# FPGA.net
KiCad netlist of a schematic drawn in Altium Designer
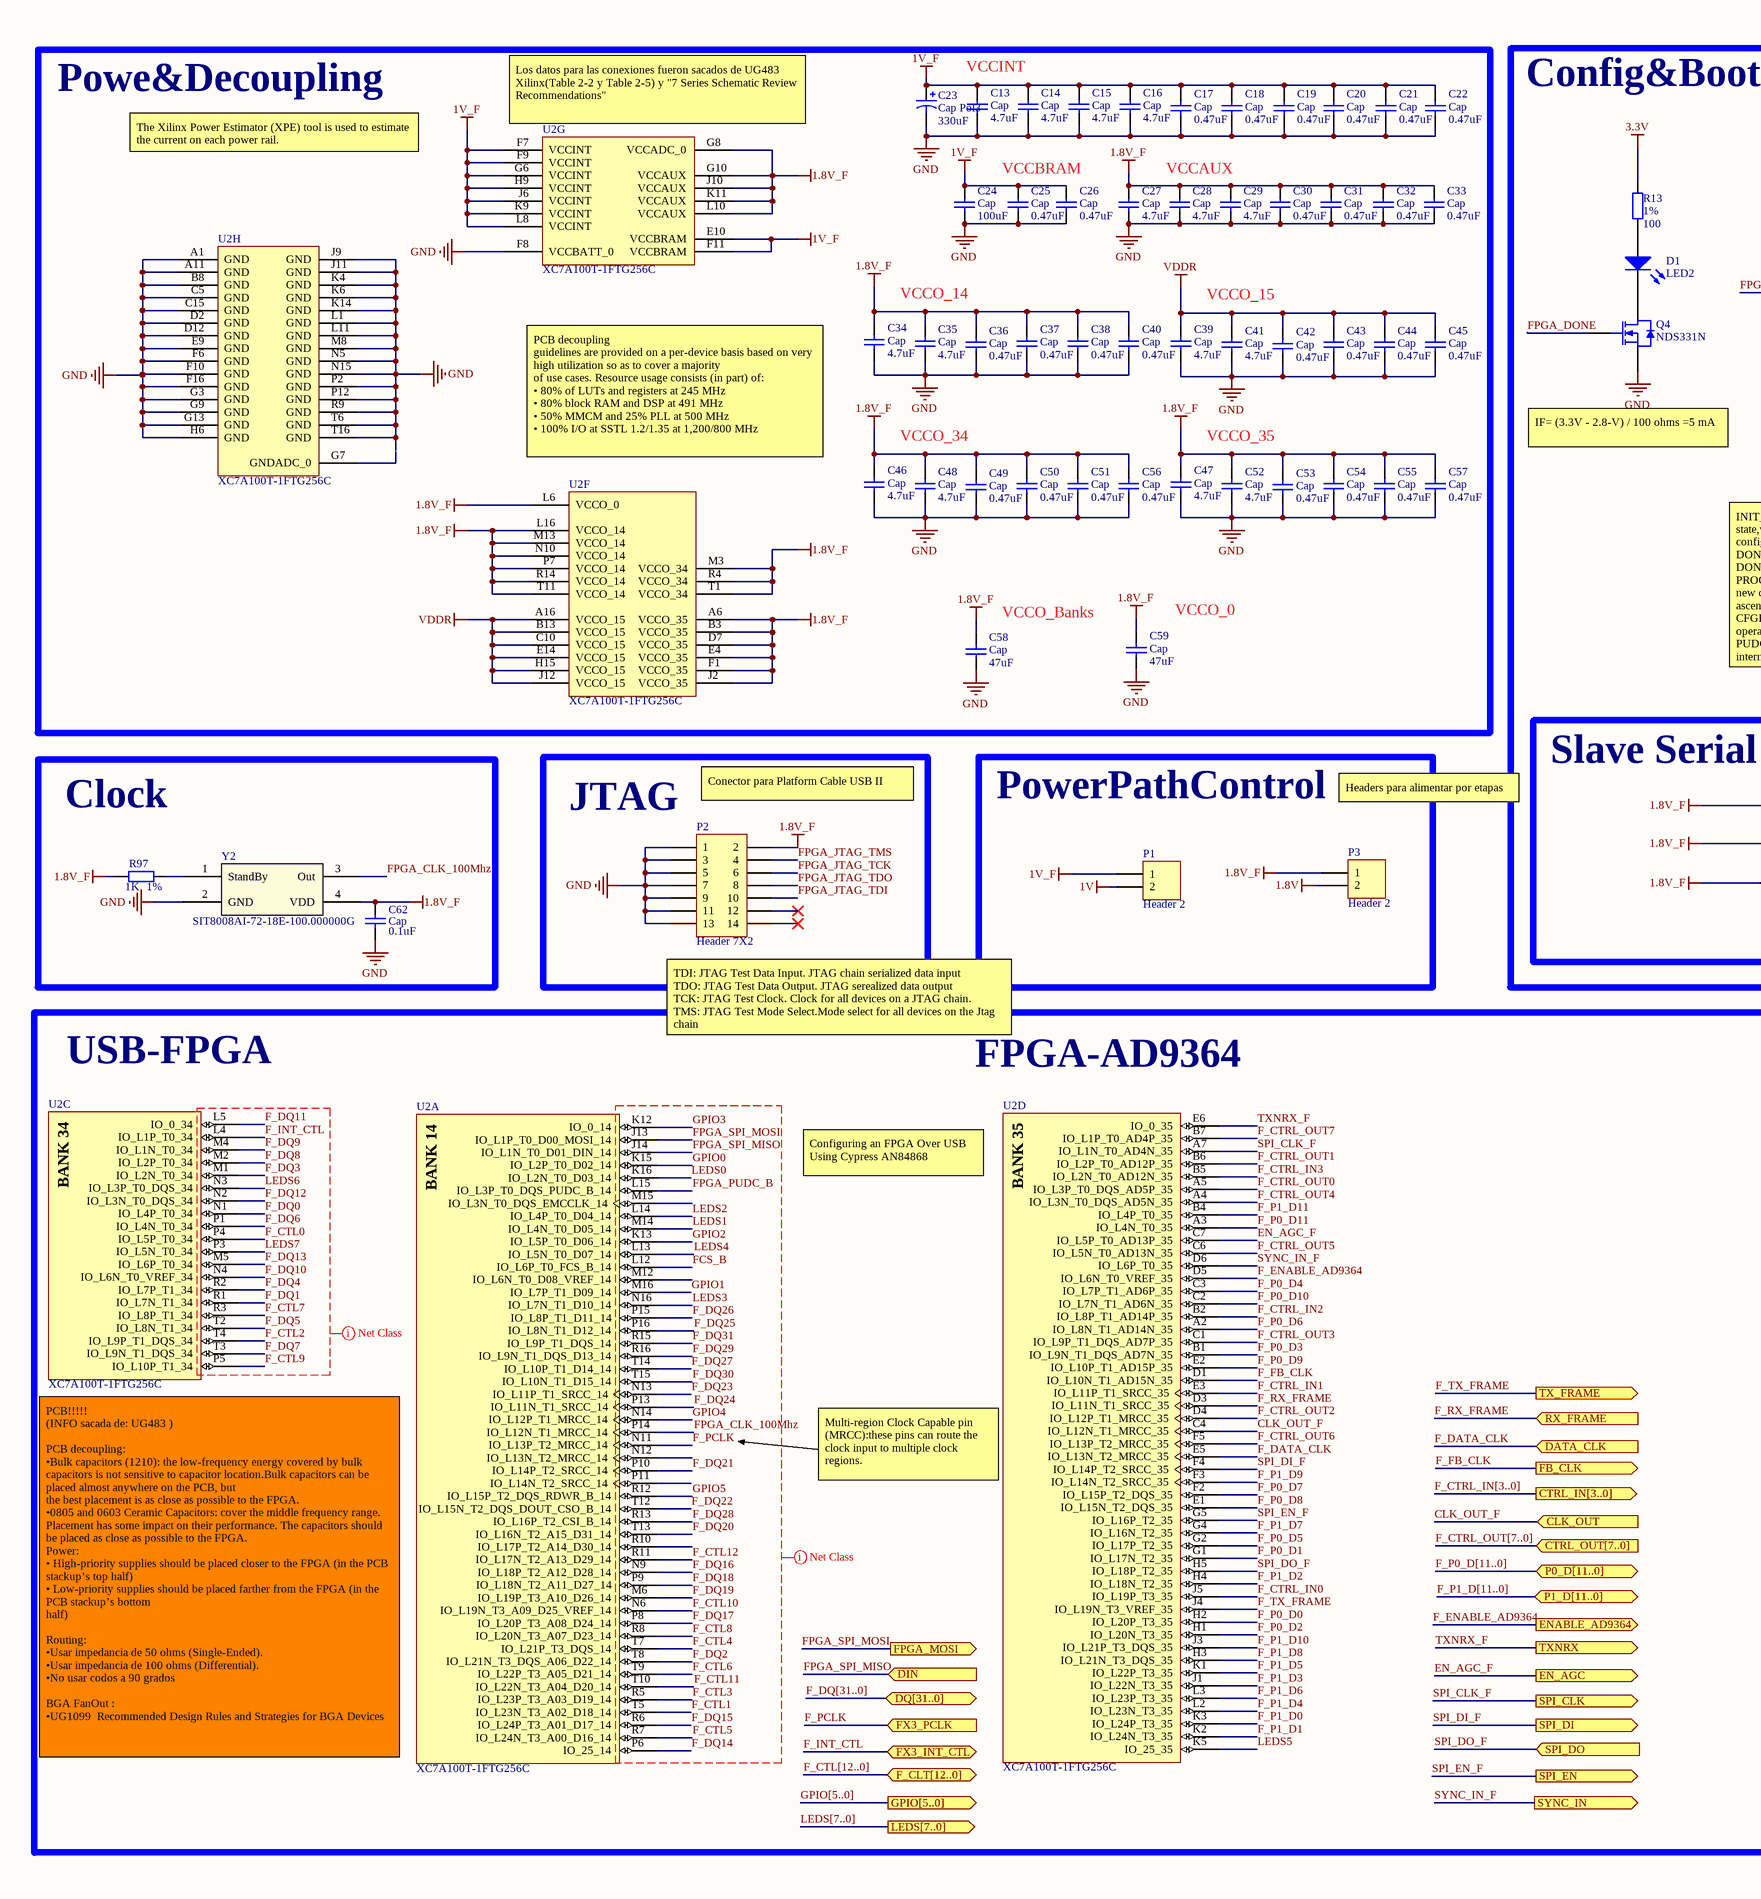
[diagram p0: FPGA.SchDoc, left]
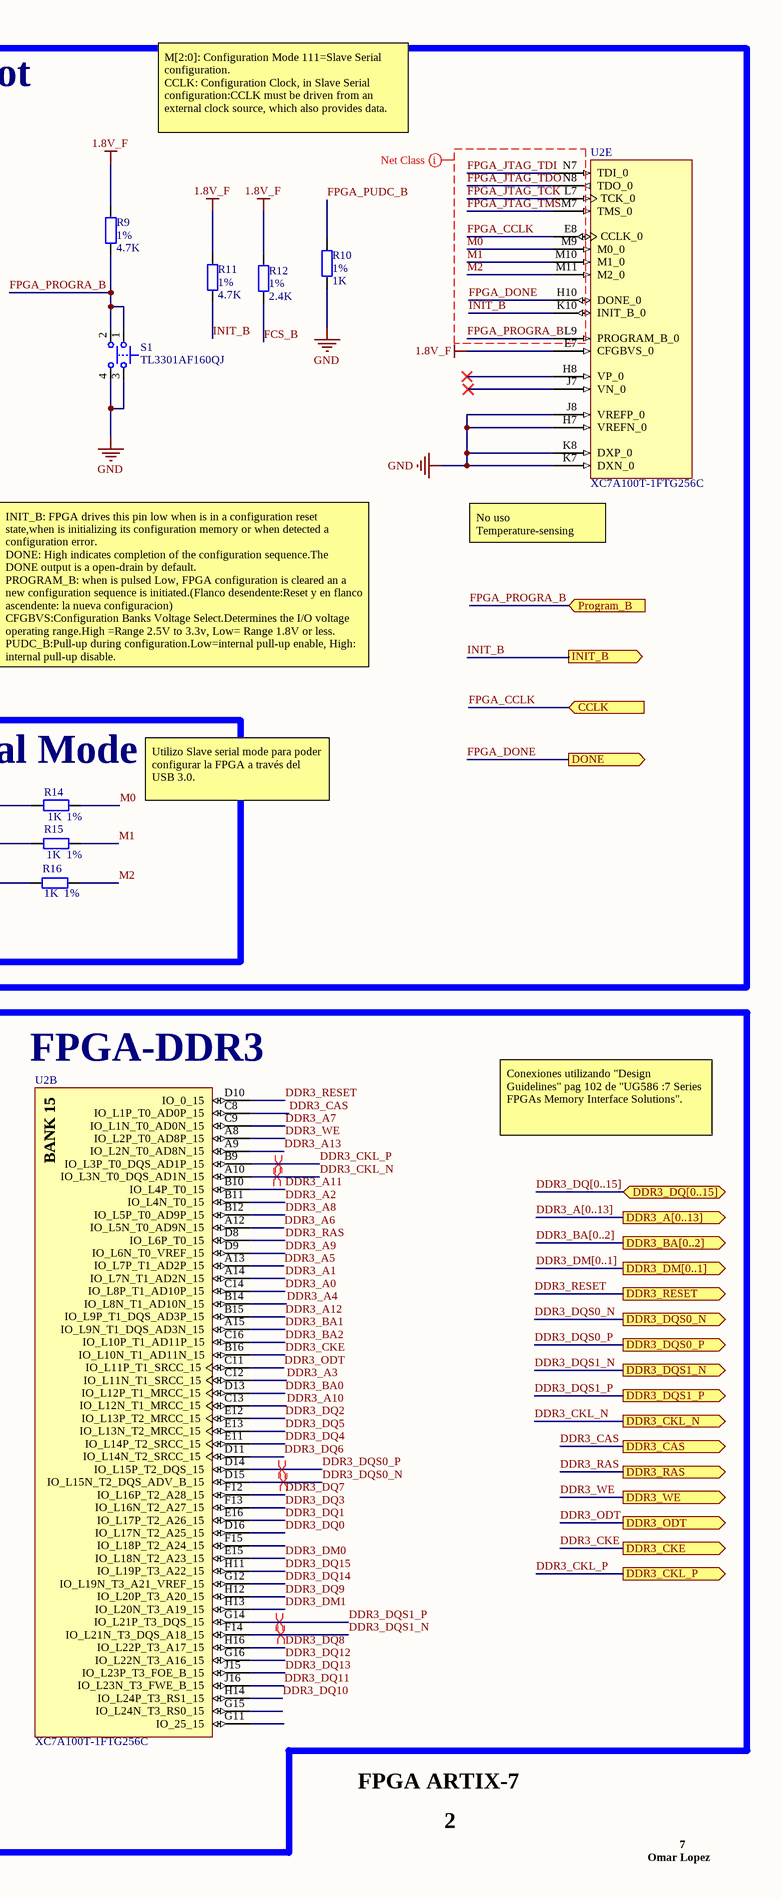
[diagram p1: FPGA.SchDoc, right]

(export (version "E")
  (design (tool "Eeschema 10.0.6"))
  (components
    (comp (ref "C13")
      (value "Cap")
      (footprint "MurataCapacitor:GRM0805MurataCap")
      (description "Capacitor")
      (fields
        (field (name "ALTIUM_VALUE") "4.7uF")
        (field (name "MANUFACTURER") "Murata")
        (field (name "TOLERANCE") "10%")
      )
      (libsource (lib "Miscellaneous Devices") (part "Cap"))
    )
    (comp (ref "C14")
      (value "Cap")
      (footprint "MurataCapacitor:GRM0805MurataCap")
      (description "Capacitor")
      (fields
        (field (name "ALTIUM_VALUE") "4.7uF")
        (field (name "MANUFACTURER") "Murata")
        (field (name "TOLERANCE") "10%")
      )
      (libsource (lib "Miscellaneous Devices") (part "Cap"))
    )
    (comp (ref "C15")
      (value "Cap")
      (footprint "MurataCapacitor:GRM0805MurataCap")
      (description "Capacitor")
      (fields
        (field (name "ALTIUM_VALUE") "4.7uF")
        (field (name "MANUFACTURER") "Murata")
        (field (name "TOLERANCE") "10%")
      )
      (libsource (lib "Miscellaneous Devices") (part "Cap"))
    )
    (comp (ref "C16")
      (value "Cap")
      (footprint "MurataCapacitor:GRM0805MurataCap")
      (description "Capacitor")
      (fields
        (field (name "ALTIUM_VALUE") "4.7uF")
        (field (name "MANUFACTURER") "Murata")
        (field (name "TOLERANCE") "10%")
      )
      (libsource (lib "Miscellaneous Devices") (part "Cap"))
    )
    (comp (ref "C17")
      (value "Cap")
      (footprint "MurataCapacitor:GRM0603MurataCap")
      (description "Capacitor")
      (fields
        (field (name "ALTIUM_VALUE") "0.47uF")
        (field (name "MANUFACTURER") "Murata")
        (field (name "TOLERANCE") "20%")
      )
      (libsource (lib "Miscellaneous Devices") (part "Cap"))
    )
    (comp (ref "C18")
      (value "Cap")
      (footprint "MurataCapacitor:GRM0603MurataCap")
      (description "Capacitor")
      (fields
        (field (name "ALTIUM_VALUE") "0.47uF")
        (field (name "MANUFACTURER") "Murata")
        (field (name "TOLERANCE") "20%")
      )
      (libsource (lib "Miscellaneous Devices") (part "Cap"))
    )
    (comp (ref "C19")
      (value "Cap")
      (footprint "MurataCapacitor:GRM0603MurataCap")
      (description "Capacitor")
      (fields
        (field (name "ALTIUM_VALUE") "0.47uF")
        (field (name "MANUFACTURER") "Murata")
        (field (name "TOLERANCE") "20%")
      )
      (libsource (lib "Miscellaneous Devices") (part "Cap"))
    )
    (comp (ref "C20")
      (value "Cap")
      (footprint "MurataCapacitor:GRM0603MurataCap")
      (description "Capacitor")
      (fields
        (field (name "ALTIUM_VALUE") "0.47uF")
        (field (name "MANUFACTURER") "Murata")
        (field (name "TOLERANCE") "20%")
      )
      (libsource (lib "Miscellaneous Devices") (part "Cap"))
    )
    (comp (ref "C21")
      (value "Cap")
      (footprint "MurataCapacitor:GRM0603MurataCap")
      (description "Capacitor")
      (fields
        (field (name "ALTIUM_VALUE") "0.47uF")
        (field (name "MANUFACTURER") "Murata")
        (field (name "TOLERANCE") "20%")
      )
      (libsource (lib "Miscellaneous Devices") (part "Cap"))
    )
    (comp (ref "C22")
      (value "Cap")
      (footprint "MurataCapacitor:GRM0603MurataCap")
      (description "Capacitor")
      (fields
        (field (name "ALTIUM_VALUE") "0.47uF")
        (field (name "MANUFACTURER") "Murata")
        (field (name "TOLERANCE") "20%")
      )
      (libsource (lib "Miscellaneous Devices") (part "Cap"))
    )
    (comp (ref "C23")
      (value "Cap Pol3")
      (footprint "T520V_CAP_330:7343")
      (description "Polarized Capacitor (Surface Mount)")
      (fields
        (field (name "ALTIUM_VALUE") "330uF")
        (field (name "TOLERANCE") "20%")
        (field (name "PARTNUMBER") "T520V337M2R5ATE025")
      )
      (libsource (lib "Miscellaneous Devices") (part "Cap Pol3"))
    )
    (comp (ref "C24")
      (value "Cap")
      (footprint "MurataCapacitor:GRM1210MurataCap")
      (description "Capacitor")
      (fields
        (field (name "ALTIUM_VALUE") "100uF")
        (field (name "MANUFACTURER") "Murata")
        (field (name "TOLERANCE") "20%")
      )
      (libsource (lib "Miscellaneous Devices") (part "Cap"))
    )
    (comp (ref "C25")
      (value "Cap")
      (footprint "MurataCapacitor:GRM0603MurataCap")
      (description "Capacitor")
      (fields
        (field (name "ALTIUM_VALUE") "0.47uF")
        (field (name "MANUFACTURER") "Murata")
        (field (name "TOLERANCE") "20%")
      )
      (libsource (lib "Miscellaneous Devices") (part "Cap"))
    )
    (comp (ref "C26")
      (value "Cap")
      (footprint "MurataCapacitor:GRM0603MurataCap")
      (description "Capacitor")
      (fields
        (field (name "ALTIUM_VALUE") "0.47uF")
        (field (name "MANUFACTURER") "Murata")
        (field (name "TOLERANCE") "20%")
      )
      (libsource (lib "Miscellaneous Devices") (part "Cap"))
    )
    (comp (ref "C27")
      (value "Cap")
      (footprint "MurataCapacitor:GRM0805MurataCap")
      (description "Capacitor")
      (fields
        (field (name "ALTIUM_VALUE") "4.7uF")
        (field (name "MANUFACTURER") "Murata")
        (field (name "TOLERANCE") "10%")
      )
      (libsource (lib "Miscellaneous Devices") (part "Cap"))
    )
    (comp (ref "C28")
      (value "Cap")
      (footprint "MurataCapacitor:GRM0805MurataCap")
      (description "Capacitor")
      (fields
        (field (name "ALTIUM_VALUE") "4.7uF")
        (field (name "MANUFACTURER") "Murata")
        (field (name "TOLERANCE") "10%")
      )
      (libsource (lib "Miscellaneous Devices") (part "Cap"))
    )
    (comp (ref "C29")
      (value "Cap")
      (footprint "MurataCapacitor:GRM0805MurataCap")
      (description "Capacitor")
      (fields
        (field (name "ALTIUM_VALUE") "4.7uF")
        (field (name "MANUFACTURER") "Murata")
        (field (name "TOLERANCE") "10%")
      )
      (libsource (lib "Miscellaneous Devices") (part "Cap"))
    )
    (comp (ref "C30")
      (value "Cap")
      (footprint "MurataCapacitor:GRM0603MurataCap")
      (description "Capacitor")
      (fields
        (field (name "ALTIUM_VALUE") "0.47uF")
        (field (name "MANUFACTURER") "Murata")
        (field (name "TOLERANCE") "20%")
      )
      (libsource (lib "Miscellaneous Devices") (part "Cap"))
    )
    (comp (ref "C31")
      (value "Cap")
      (footprint "MurataCapacitor:GRM0603MurataCap")
      (description "Capacitor")
      (fields
        (field (name "ALTIUM_VALUE") "0.47uF")
        (field (name "MANUFACTURER") "Murata")
        (field (name "TOLERANCE") "20%")
      )
      (libsource (lib "Miscellaneous Devices") (part "Cap"))
    )
    (comp (ref "C32")
      (value "Cap")
      (footprint "MurataCapacitor:GRM0603MurataCap")
      (description "Capacitor")
      (fields
        (field (name "ALTIUM_VALUE") "0.47uF")
        (field (name "MANUFACTURER") "Murata")
        (field (name "TOLERANCE") "20%")
      )
      (libsource (lib "Miscellaneous Devices") (part "Cap"))
    )
    (comp (ref "C33")
      (value "Cap")
      (footprint "MurataCapacitor:GRM0603MurataCap")
      (description "Capacitor")
      (fields
        (field (name "ALTIUM_VALUE") "0.47uF")
        (field (name "MANUFACTURER") "Murata")
        (field (name "TOLERANCE") "20%")
      )
      (libsource (lib "Miscellaneous Devices") (part "Cap"))
    )
    (comp (ref "C34")
      (value "Cap")
      (footprint "MurataCapacitor:GRM0805MurataCap")
      (description "Capacitor")
      (fields
        (field (name "ALTIUM_VALUE") "4.7uF")
        (field (name "MANUFACTURER") "Murata")
        (field (name "TOLERANCE") "10%")
      )
      (libsource (lib "Miscellaneous Devices") (part "Cap"))
    )
    (comp (ref "C35")
      (value "Cap")
      (footprint "MurataCapacitor:GRM0805MurataCap")
      (description "Capacitor")
      (fields
        (field (name "ALTIUM_VALUE") "4.7uF")
        (field (name "MANUFACTURER") "Murata")
        (field (name "TOLERANCE") "10%")
      )
      (libsource (lib "Miscellaneous Devices") (part "Cap"))
    )
    (comp (ref "C36")
      (value "Cap")
      (footprint "MurataCapacitor:GRM0603MurataCap")
      (description "Capacitor")
      (fields
        (field (name "ALTIUM_VALUE") "0.47uF")
        (field (name "MANUFACTURER") "Murata")
        (field (name "TOLERANCE") "20%")
      )
      (libsource (lib "Miscellaneous Devices") (part "Cap"))
    )
    (comp (ref "C37")
      (value "Cap")
      (footprint "MurataCapacitor:GRM0603MurataCap")
      (description "Capacitor")
      (fields
        (field (name "ALTIUM_VALUE") "0.47uF")
        (field (name "MANUFACTURER") "Murata")
        (field (name "TOLERANCE") "20%")
      )
      (libsource (lib "Miscellaneous Devices") (part "Cap"))
    )
    (comp (ref "C38")
      (value "Cap")
      (footprint "MurataCapacitor:GRM0603MurataCap")
      (description "Capacitor")
      (fields
        (field (name "ALTIUM_VALUE") "0.47uF")
        (field (name "MANUFACTURER") "Murata")
        (field (name "TOLERANCE") "20%")
      )
      (libsource (lib "Miscellaneous Devices") (part "Cap"))
    )
    (comp (ref "C39")
      (value "Cap")
      (footprint "MurataCapacitor:GRM0805MurataCap")
      (description "Capacitor")
      (fields
        (field (name "ALTIUM_VALUE") "4.7uF")
        (field (name "MANUFACTURER") "Murata")
        (field (name "TOLERANCE") "10%")
      )
      (libsource (lib "Miscellaneous Devices") (part "Cap"))
    )
    (comp (ref "C40")
      (value "Cap")
      (footprint "MurataCapacitor:GRM0603MurataCap")
      (description "Capacitor")
      (fields
        (field (name "ALTIUM_VALUE") "0.47uF")
        (field (name "MANUFACTURER") "Murata")
        (field (name "TOLERANCE") "20%")
      )
      (libsource (lib "Miscellaneous Devices") (part "Cap"))
    )
    (comp (ref "C41")
      (value "Cap")
      (footprint "MurataCapacitor:GRM0805MurataCap")
      (description "Capacitor")
      (fields
        (field (name "ALTIUM_VALUE") "4.7uF")
        (field (name "MANUFACTURER") "Murata")
        (field (name "TOLERANCE") "10%")
      )
      (libsource (lib "Miscellaneous Devices") (part "Cap"))
    )
    (comp (ref "C42")
      (value "Cap")
      (footprint "MurataCapacitor:GRM0603MurataCap")
      (description "Capacitor")
      (fields
        (field (name "ALTIUM_VALUE") "0.47uF")
        (field (name "MANUFACTURER") "Murata")
        (field (name "TOLERANCE") "20%")
      )
      (libsource (lib "Miscellaneous Devices") (part "Cap"))
    )
    (comp (ref "C43")
      (value "Cap")
      (footprint "MurataCapacitor:GRM0603MurataCap")
      (description "Capacitor")
      (fields
        (field (name "ALTIUM_VALUE") "0.47uF")
        (field (name "MANUFACTURER") "Murata")
        (field (name "TOLERANCE") "20%")
      )
      (libsource (lib "Miscellaneous Devices") (part "Cap"))
    )
    (comp (ref "C44")
      (value "Cap")
      (footprint "MurataCapacitor:GRM0603MurataCap")
      (description "Capacitor")
      (fields
        (field (name "ALTIUM_VALUE") "0.47uF")
        (field (name "MANUFACTURER") "Murata")
        (field (name "TOLERANCE") "20%")
      )
      (libsource (lib "Miscellaneous Devices") (part "Cap"))
    )
    (comp (ref "C45")
      (value "Cap")
      (footprint "MurataCapacitor:GRM0603MurataCap")
      (description "Capacitor")
      (fields
        (field (name "ALTIUM_VALUE") "0.47uF")
        (field (name "MANUFACTURER") "Murata")
        (field (name "TOLERANCE") "20%")
      )
      (libsource (lib "Miscellaneous Devices") (part "Cap"))
    )
    (comp (ref "C46")
      (value "Cap")
      (footprint "MurataCapacitor:GRM0805MurataCap")
      (description "Capacitor")
      (fields
        (field (name "ALTIUM_VALUE") "4.7uF")
        (field (name "MANUFACTURER") "Murata")
        (field (name "TOLERANCE") "10%")
      )
      (libsource (lib "Miscellaneous Devices") (part "Cap"))
    )
    (comp (ref "C47")
      (value "Cap")
      (footprint "MurataCapacitor:GRM0805MurataCap")
      (description "Capacitor")
      (fields
        (field (name "ALTIUM_VALUE") "4.7uF")
        (field (name "MANUFACTURER") "Murata")
        (field (name "TOLERANCE") "10%")
      )
      (libsource (lib "Miscellaneous Devices") (part "Cap"))
    )
    (comp (ref "C48")
      (value "Cap")
      (footprint "MurataCapacitor:GRM0805MurataCap")
      (description "Capacitor")
      (fields
        (field (name "ALTIUM_VALUE") "4.7uF")
        (field (name "MANUFACTURER") "Murata")
        (field (name "TOLERANCE") "10%")
      )
      (libsource (lib "Miscellaneous Devices") (part "Cap"))
    )
    (comp (ref "C49")
      (value "Cap")
      (footprint "MurataCapacitor:GRM0603MurataCap")
      (description "Capacitor")
      (fields
        (field (name "ALTIUM_VALUE") "0.47uF")
        (field (name "MANUFACTURER") "Murata")
        (field (name "TOLERANCE") "20%")
      )
      (libsource (lib "Miscellaneous Devices") (part "Cap"))
    )
    (comp (ref "C50")
      (value "Cap")
      (footprint "MurataCapacitor:GRM0603MurataCap")
      (description "Capacitor")
      (fields
        (field (name "ALTIUM_VALUE") "0.47uF")
        (field (name "MANUFACTURER") "Murata")
        (field (name "TOLERANCE") "20%")
      )
      (libsource (lib "Miscellaneous Devices") (part "Cap"))
    )
    (comp (ref "C51")
      (value "Cap")
      (footprint "MurataCapacitor:GRM0603MurataCap")
      (description "Capacitor")
      (fields
        (field (name "ALTIUM_VALUE") "0.47uF")
        (field (name "MANUFACTURER") "Murata")
        (field (name "TOLERANCE") "20%")
      )
      (libsource (lib "Miscellaneous Devices") (part "Cap"))
    )
    (comp (ref "C52")
      (value "Cap")
      (footprint "MurataCapacitor:GRM0805MurataCap")
      (description "Capacitor")
      (fields
        (field (name "ALTIUM_VALUE") "4.7uF")
        (field (name "MANUFACTURER") "Murata")
        (field (name "TOLERANCE") "10%")
      )
      (libsource (lib "Miscellaneous Devices") (part "Cap"))
    )
    (comp (ref "C53")
      (value "Cap")
      (footprint "MurataCapacitor:GRM0603MurataCap")
      (description "Capacitor")
      (fields
        (field (name "ALTIUM_VALUE") "0.47uF")
        (field (name "MANUFACTURER") "Murata")
        (field (name "TOLERANCE") "20%")
      )
      (libsource (lib "Miscellaneous Devices") (part "Cap"))
    )
    (comp (ref "C54")
      (value "Cap")
      (footprint "MurataCapacitor:GRM0603MurataCap")
      (description "Capacitor")
      (fields
        (field (name "ALTIUM_VALUE") "0.47uF")
        (field (name "MANUFACTURER") "Murata")
        (field (name "TOLERANCE") "20%")
      )
      (libsource (lib "Miscellaneous Devices") (part "Cap"))
    )
    (comp (ref "C55")
      (value "Cap")
      (footprint "MurataCapacitor:GRM0603MurataCap")
      (description "Capacitor")
      (fields
        (field (name "ALTIUM_VALUE") "0.47uF")
        (field (name "MANUFACTURER") "Murata")
        (field (name "TOLERANCE") "20%")
      )
      (libsource (lib "Miscellaneous Devices") (part "Cap"))
    )
    (comp (ref "C56")
      (value "Cap")
      (footprint "MurataCapacitor:GRM0603MurataCap")
      (description "Capacitor")
      (fields
        (field (name "ALTIUM_VALUE") "0.47uF")
        (field (name "MANUFACTURER") "Murata")
        (field (name "TOLERANCE") "20%")
      )
      (libsource (lib "Miscellaneous Devices") (part "Cap"))
    )
    (comp (ref "C57")
      (value "Cap")
      (footprint "MurataCapacitor:GRM0603MurataCap")
      (description "Capacitor")
      (fields
        (field (name "ALTIUM_VALUE") "0.47uF")
        (field (name "MANUFACTURER") "Murata")
        (field (name "TOLERANCE") "20%")
      )
      (libsource (lib "Miscellaneous Devices") (part "Cap"))
    )
    (comp (ref "C58")
      (value "Cap")
      (footprint "MurataCapacitor:GRM1210MurataCap")
      (description "Capacitor")
      (fields
        (field (name "ALTIUM_VALUE") "47uF")
        (field (name "MANUFACTURER") "Murata")
        (field (name "TOLERANCE") "10%")
      )
      (libsource (lib "Miscellaneous Devices") (part "Cap"))
    )
    (comp (ref "C59")
      (value "Cap")
      (footprint "MurataCapacitor:GRM1210MurataCap")
      (description "Capacitor")
      (fields
        (field (name "ALTIUM_VALUE") "47uF")
        (field (name "MANUFACTURER") "Murata")
        (field (name "TOLERANCE") "10%")
      )
      (libsource (lib "Miscellaneous Devices") (part "Cap"))
    )
    (comp (ref "C62")
      (value "Cap")
      (footprint "GRM0402MurataCap")
      (description "Capacitor")
      (fields
        (field (name "MANUFACTURER") "Murata")
        (field (name "PARTNUMBER") "GRM152D70G104ME15D")
        (field (name "ALTIUM_VALUE") "0.1uF")
      )
      (libsource (lib "Miscellaneous Devices") (part "Cap"))
    )
    (comp (ref "D1")
      (value "LED2")
      (footprint "LiteOnLed:LTSTC191")
      (description "Typical RED, GREEN, YELLOW, AMBER GaAs LED")
      (fields (field (name "MANUFACTURER") "Panasonic") (field (name "PARTNUMBER") "LTST-C193TGKT-5A"))
      (libsource (lib "Miscellaneous Devices") (part "LED2"))
    )
    (comp (ref "P1")
      (value "Header 2")
      (footprint "Header2x1")
      (description "Header, 2-Pin")
      (fields (field (name "MANUFACTURER") "TE Connectivity") (field (name "PARTNUMBER") "826629"))
      (libsource (lib "Miscellaneous Connectors") (part "Header 2"))
    )
    (comp (ref "P2")
      (value "Header 7X2")
      (footprint "header2x7:MolexHeader2x7_")
      (description "Header, 7-Pin, Dual row")
      (fields (field (name "MANUFACTURER") "Molex") (field (name "PARTNUMBER") "87832-1420"))
      (libsource (lib "Miscellaneous Connectors") (part "Header 7X2"))
    )
    (comp (ref "P3")
      (value "Header 2")
      (footprint "Header2x1")
      (description "Header, 2-Pin")
      (fields (field (name "MANUFACTURER") "TE Connectivity") (field (name "PARTNUMBER") "826629"))
      (libsource (lib "Miscellaneous Connectors") (part "Header 2"))
    )
    (comp (ref "Q4")
      (value "NDS331N")
      (footprint "ON_Semi_527AG-01_0")
      (description "N-Channel 60V (D-S), 175'C  MOSFET")
      (fields (field (name "MANUFACTURER") "On Semiconductor"))
      (libsource (lib "Vishay Siliconix Discrete MOSFET") (part "SUP70N06-14"))
    )
    (comp (ref "R9")
      (value "1%")
      (footprint "Res0402ERJ:RC0402N")
      (description "Resistor")
      (fields
        (field (name "ALTIUM_VALUE") "4.7K")
        (field (name "MANUFACTURER") "Panasonic")
        (field (name "PARTNUMBER") "ERJ-2RKF4701X")
      )
      (libsource (lib "") (part "Res2_2"))
    )
    (comp (ref "R10")
      (value "1%")
      (footprint "Res0402ERJ:RC0402N")
      (description "Resistor")
      (fields
        (field (name "ALTIUM_VALUE") "1K")
        (field (name "MANUFACTURER") "Panasonic")
        (field (name "PARTNUMBER") "ERJ-PA2F1001X")
      )
      (libsource (lib "") (part "Res2_3"))
    )
    (comp (ref "R11")
      (value "1%")
      (footprint "Res0402ERJ:RC0402N")
      (description "Resistor")
      (fields
        (field (name "ALTIUM_VALUE") "4.7K")
        (field (name "MANUFACTURER") "Panasonic")
        (field (name "PARTNUMBER") "ERJ-2RKF4701X")
      )
      (libsource (lib "") (part "Res2_2"))
    )
    (comp (ref "R12")
      (value "1%")
      (footprint "Res0402ERJ:RC0402N")
      (description "Resistor")
      (fields
        (field (name "ALTIUM_VALUE") "2.4K")
        (field (name "MANUFACTURER") "Panasonic")
        (field (name "PARTNUMBER") "ERJ-2RKF2401X")
      )
      (libsource (lib "") (part "Res2_2"))
    )
    (comp (ref "R13")
      (value "1%")
      (footprint "Res0402ERJ:RC0402N")
      (description "Resistor")
      (fields
        (field (name "ALTIUM_VALUE") "100")
        (field (name "MANUFACTURER") "Panasonic")
        (field (name "PARTNUMBER") "ERJ-2RKF4701X")
      )
      (libsource (lib "") (part "Res2_2"))
    )
    (comp (ref "R14")
      (value "1%")
      (footprint "Res0402ERJ:RC0402N")
      (description "Resistor")
      (fields
        (field (name "ALTIUM_VALUE") "1K")
        (field (name "MANUFACTURER") "Panasonic")
        (field (name "PARTNUMBER") "ERJ-PA2F1001X")
      )
      (libsource (lib "Miscellaneous Devices") (part "Res2"))
    )
    (comp (ref "R15")
      (value "1%")
      (footprint "Res0402ERJ:RC0402N")
      (description "Resistor")
      (fields
        (field (name "ALTIUM_VALUE") "1K")
        (field (name "MANUFACTURER") "Panasonic")
        (field (name "PARTNUMBER") "ERJ-PA2F1001X")
      )
      (libsource (lib "Miscellaneous Devices") (part "Res2"))
    )
    (comp (ref "R16")
      (value "1%")
      (footprint "Res0402ERJ:RC0402N")
      (description "Resistor")
      (fields
        (field (name "ALTIUM_VALUE") "1K")
        (field (name "MANUFACTURER") "Panasonic")
        (field (name "PARTNUMBER") "ERJ-PA2F1001X")
      )
      (libsource (lib "Miscellaneous Devices") (part "Res2"))
    )
    (comp (ref "R97")
      (value "1%")
      (footprint "Res0402ERJ:RC0402N")
      (description "Resistor")
      (fields
        (field (name "ALTIUM_VALUE") "1K")
        (field (name "MANUFACTURER") "Panasonic")
        (field (name "PARTNUMBER") "ERJ-PA2F1001X")
      )
      (libsource (lib "") (part "Res2_1"))
    )
    (comp (ref "S1")
      (value "TL3301AF160QJ")
      (footprint "ButtonE-Switch:TL3301AF160QJ")
      (description "Tactile Switch, DPST; Thru-Hole; Vertical; Rating DC 12V, 50mA (max)")
      (fields (field (name "MANUFACTURER") "E-Switch"))
      (libsource (lib "IL Switch Push Button") (part "IT-2175"))
    )
    (comp (ref "U2")
      (value "XC7A100T-1FTG256C")
      (footprint "Xilinx Artix-7:FTG256")
      (description "Artix-7 FPGA, 170 User I/Os, 0 GTP, 256-Ball BGA, Speed Grade 1, Commercial Grade, Pb-Free")
      (fields (field (name "MANUFACTURER") "Xilinx Inc.") (field (name "PARTNUMBER") "XC7A75T-1FTG256C"))
      (libsource (lib "Xilinx Artix-7") (part "XC7A35T-1FTG256C"))
    )
    (comp (ref "Y2")
      (value "SIT8008AI-72-18E-100.000000G")
      (footprint "SiT8008AI-72-18E-100.000000G:SiT2002AI-72-18E-100.000000G")
      (description "Crystal")
      (fields (field (name "MANUFACTURER") "SiTIME") (field (name "TOLERANCE") "20 PPM"))
      (libsource (lib "ASEM1-100.000MHZ-LC-T") (part "ASEM1-100.000MHZ-LC-T"))
    )
  )
  (nets
    (net (code "1") (name "/CLK_OUT_F") (class "Default")
      (node (ref "U2") (pin "C4") (pinfunction "IO_L12N_T1_MRCC_35_C4") (pintype "bidirectional"))
    )
    (net (code "2") (name "/DDR3_A0") (class "Default")
      (node (ref "U2") (pin "C14") (pinfunction "IO_L8P_T1_AD10P_15_C14") (pintype "bidirectional"))
    )
    (net (code "3") (name "/DDR3_A1") (class "Default")
      (node (ref "U2") (pin "A14") (pinfunction "IO_L7N_T1_AD2N_15_A14") (pintype "bidirectional"))
    )
    (net (code "4") (name "/DDR3_A2") (class "Default")
      (node (ref "U2") (pin "B11") (pinfunction "IO_L4N_T0_15_B11") (pintype "bidirectional"))
    )
    (net (code "5") (name "/DDR3_A3") (class "Default")
      (node (ref "U2") (pin "C12") (pinfunction "IO_L11N_T1_SRCC_15_C12") (pintype "bidirectional"))
    )
    (net (code "6") (name "/DDR3_A4") (class "Default")
      (node (ref "U2") (pin "B14") (pinfunction "IO_L8N_T1_AD10N_15_B14") (pintype "bidirectional"))
    )
    (net (code "7") (name "/DDR3_A5") (class "Default")
      (node (ref "U2") (pin "A13") (pinfunction "IO_L7P_T1_AD2P_15_A13") (pintype "bidirectional"))
    )
    (net (code "8") (name "/DDR3_A6") (class "Default")
      (node (ref "U2") (pin "A12") (pinfunction "IO_L5N_T0_AD9N_15_A12") (pintype "bidirectional"))
    )
    (net (code "9") (name "/DDR3_A7") (class "Default")
      (node (ref "U2") (pin "C9") (pinfunction "IO_L1N_T0_AD0N_15_C9") (pintype "bidirectional"))
    )
    (net (code "10") (name "/DDR3_A8") (class "Default")
      (node (ref "U2") (pin "B12") (pinfunction "IO_L5P_T0_AD9P_15_B12") (pintype "bidirectional"))
    )
    (net (code "11") (name "/DDR3_A9") (class "Default")
      (node (ref "U2") (pin "D9") (pinfunction "IO_L6N_T0_VREF_15_D9") (pintype "bidirectional"))
    )
    (net (code "12") (name "/DDR3_A10") (class "Default")
      (node (ref "U2") (pin "C13") (pinfunction "IO_L12N_T1_MRCC_15_C13") (pintype "bidirectional"))
    )
    (net (code "13") (name "/DDR3_A11") (class "Default")
      (node (ref "U2") (pin "B10") (pinfunction "IO_L4P_T0_15_B10") (pintype "bidirectional"))
    )
    (net (code "14") (name "/DDR3_A12") (class "Default")
      (node (ref "U2") (pin "B15") (pinfunction "IO_L9P_T1_DQS_AD3P_15_B15") (pintype "bidirectional"))
    )
    (net (code "15") (name "/DDR3_A13") (class "Default")
      (node (ref "U2") (pin "A9") (pinfunction "IO_L2N_T0_AD8N_15_A9") (pintype "bidirectional"))
    )
    (net (code "17") (name "/DDR3_BA0") (class "Default")
      (node (ref "U2") (pin "D13") (pinfunction "IO_L12P_T1_MRCC_15_D13") (pintype "bidirectional"))
    )
    (net (code "18") (name "/DDR3_BA1") (class "Default")
      (node (ref "U2") (pin "A15") (pinfunction "IO_L9N_T1_DQS_AD3N_15_A15") (pintype "bidirectional"))
    )
    (net (code "19") (name "/DDR3_BA2") (class "Default")
      (node (ref "U2") (pin "C16") (pinfunction "IO_L10P_T1_AD11P_15_C16") (pintype "bidirectional"))
    )
    (net (code "21") (name "/DDR3_CAS") (class "Default")
      (node (ref "U2") (pin "C8") (pinfunction "IO_L1P_T0_AD0P_15_C8") (pintype "bidirectional"))
    )
    (net (code "22") (name "/DDR3_CKE") (class "Default")
      (node (ref "U2") (pin "B16") (pinfunction "IO_L10N_T1_AD11N_15_B16") (pintype "bidirectional"))
    )
    (net (code "23") (name "/DDR3_CKL_N") (class "Default")
      (node (ref "U2") (pin "A10") (pinfunction "IO_L3N_T0_DQS_AD1N_15_A10") (pintype "bidirectional"))
    )
    (net (code "24") (name "/DDR3_CKL_P") (class "Default")
      (node (ref "U2") (pin "B9") (pinfunction "IO_L3P_T0_DQS_AD1P_15_B9") (pintype "bidirectional"))
    )
    (net (code "25") (name "/DDR3_DM0") (class "Default")
      (node (ref "U2") (pin "E15") (pinfunction "IO_L18N_T2_A23_15_E15") (pintype "bidirectional"))
    )
    (net (code "26") (name "/DDR3_DM1") (class "Default")
      (node (ref "U2") (pin "H13") (pinfunction "IO_L20N_T3_A19_15_H13") (pintype "bidirectional"))
    )
    (net (code "28") (name "/DDR3_DQ0") (class "Default")
      (node (ref "U2") (pin "D16") (pinfunction "IO_L17N_T2_A25_15_D16") (pintype "bidirectional"))
    )
    (net (code "29") (name "/DDR3_DQ1") (class "Default")
      (node (ref "U2") (pin "E16") (pinfunction "IO_L17P_T2_A26_15_E16") (pintype "bidirectional"))
    )
    (net (code "30") (name "/DDR3_DQ2") (class "Default")
      (node (ref "U2") (pin "E12") (pinfunction "IO_L13P_T2_MRCC_15_E12") (pintype "bidirectional"))
    )
    (net (code "31") (name "/DDR3_DQ3") (class "Default")
      (node (ref "U2") (pin "F13") (pinfunction "IO_L16N_T2_A27_15_F13") (pintype "bidirectional"))
    )
    (net (code "32") (name "/DDR3_DQ4") (class "Default")
      (node (ref "U2") (pin "E11") (pinfunction "IO_L14P_T2_SRCC_15_E11") (pintype "bidirectional"))
    )
    (net (code "33") (name "/DDR3_DQ5") (class "Default")
      (node (ref "U2") (pin "E13") (pinfunction "IO_L13N_T2_MRCC_15_E13") (pintype "bidirectional"))
    )
    (net (code "34") (name "/DDR3_DQ6") (class "Default")
      (node (ref "U2") (pin "D11") (pinfunction "IO_L14N_T2_SRCC_15_D11") (pintype "bidirectional"))
    )
    (net (code "35") (name "/DDR3_DQ7") (class "Default")
      (node (ref "U2") (pin "F12") (pinfunction "IO_L16P_T2_A28_15_F12") (pintype "bidirectional"))
    )
    (net (code "36") (name "/DDR3_DQ8") (class "Default")
      (node (ref "U2") (pin "H16") (pinfunction "IO_L22P_T3_A17_15_H16") (pintype "bidirectional"))
    )
    (net (code "37") (name "/DDR3_DQ9") (class "Default")
      (node (ref "U2") (pin "H12") (pinfunction "IO_L20P_T3_A20_15_H12") (pintype "bidirectional"))
    )
    (net (code "38") (name "/DDR3_DQ10") (class "Default")
      (node (ref "U2") (pin "H14") (pinfunction "IO_L24P_T3_RS1_15_H14") (pintype "bidirectional"))
    )
    (net (code "39") (name "/DDR3_DQ11") (class "Default")
      (node (ref "U2") (pin "J16") (pinfunction "IO_L23N_T3_FWE_B_15_J16") (pintype "bidirectional"))
    )
    (net (code "40") (name "/DDR3_DQ12") (class "Default")
      (node (ref "U2") (pin "G16") (pinfunction "IO_L22N_T3_A16_15_G16") (pintype "bidirectional"))
    )
    (net (code "41") (name "/DDR3_DQ13") (class "Default")
      (node (ref "U2") (pin "J15") (pinfunction "IO_L23P_T3_FOE_B_15_J15") (pintype "bidirectional"))
    )
    (net (code "42") (name "/DDR3_DQ14") (class "Default")
      (node (ref "U2") (pin "G12") (pinfunction "IO_L19N_T3_A21_VREF_15_G12") (pintype "bidirectional"))
    )
    (net (code "43") (name "/DDR3_DQ15") (class "Default")
      (node (ref "U2") (pin "H11") (pinfunction "IO_L19P_T3_A22_15_H11") (pintype "bidirectional"))
    )
    (net (code "44") (name "/DDR3_DQS0_N") (class "Default")
      (node (ref "U2") (pin "D15") (pinfunction "IO_L15N_T2_DQS_ADV_B_15_D15") (pintype "bidirectional"))
    )
    (net (code "45") (name "/DDR3_DQS0_P") (class "Default")
      (node (ref "U2") (pin "D14") (pinfunction "IO_L15P_T2_DQS_15_D14") (pintype "bidirectional"))
    )
    (net (code "46") (name "/DDR3_DQS1_N") (class "Default")
      (node (ref "U2") (pin "F14") (pinfunction "IO_L21N_T3_DQS_A18_15_F14") (pintype "bidirectional"))
    )
    (net (code "47") (name "/DDR3_DQS1_P") (class "Default")
      (node (ref "U2") (pin "G14") (pinfunction "IO_L21P_T3_DQS_15_G14") (pintype "bidirectional"))
    )
    (net (code "49") (name "/DDR3_ODT") (class "Default")
      (node (ref "U2") (pin "C11") (pinfunction "IO_L11P_T1_SRCC_15_C11") (pintype "bidirectional"))
    )
    (net (code "50") (name "/DDR3_RAS") (class "Default")
      (node (ref "U2") (pin "D8") (pinfunction "IO_L6P_T0_15_D8") (pintype "bidirectional"))
    )
    (net (code "51") (name "/DDR3_RESET") (class "Default")
      (node (ref "U2") (pin "D10") (pinfunction "IO_0_15_D10") (pintype "bidirectional"))
    )
    (net (code "52") (name "/DDR3_WE") (class "Default")
      (node (ref "U2") (pin "A8") (pinfunction "IO_L2P_T0_AD8P_15_A8") (pintype "bidirectional"))
    )
    (net (code "53") (name "/EN_AGC_F") (class "Default")
      (node (ref "U2") (pin "C7") (pinfunction "IO_L5P_T0_AD13P_35_C7") (pintype "bidirectional"))
    )
    (net (code "54") (name "/FCS_B") (class "Default")
      (node (ref "R12") (pin "1") (pinfunction "1_1") (pintype "passive"))
      (node (ref "U2") (pin "L12") (pinfunction "IO_L6P_T0_FCS_B_14_L12") (pintype "bidirectional"))
    )
    (net (code "55") (name "/FPGA_CCLK") (class "Default")
      (node (ref "U2") (pin "E8") (pinfunction "CCLK_0_E8") (pintype "bidirectional"))
    )
    (net (code "56") (name "/FPGA_CLK_100Mhz") (class "Default")
      (node (ref "U2") (pin "P14") (pinfunction "IO_L12N_T1_MRCC_14_P14") (pintype "bidirectional"))
      (node (ref "Y2") (pin "3") (pinfunction "Out_3") (pintype "passive"))
    )
    (net (code "57") (name "/FPGA_DONE") (class "Default")
      (node (ref "Q4") (pin "1") (pinfunction "G_1") (pintype "passive"))
      (node (ref "U2") (pin "H10") (pinfunction "DONE_0_H10") (pintype "bidirectional"))
    )
    (net (code "58") (name "/FPGA_JTAG_TCK") (class "Default")
      (node (ref "P2") (pin "6") (pinfunction "6_6") (pintype "passive"))
      (node (ref "U2") (pin "L7") (pinfunction "TCK_0_L7") (pintype "input"))
    )
    (net (code "59") (name "/FPGA_JTAG_TDI") (class "Default")
      (node (ref "P2") (pin "10") (pinfunction "10_10") (pintype "passive"))
      (node (ref "U2") (pin "N7") (pinfunction "TDI_0_N7") (pintype "input"))
    )
    (net (code "60") (name "/FPGA_JTAG_TDO") (class "Default")
      (node (ref "P2") (pin "8") (pinfunction "8_8") (pintype "passive"))
      (node (ref "U2") (pin "N8") (pinfunction "TDO_0_N8") (pintype "output"))
    )
    (net (code "61") (name "/FPGA_JTAG_TMS") (class "Default")
      (node (ref "P2") (pin "4") (pinfunction "4_4") (pintype "passive"))
      (node (ref "U2") (pin "M7") (pinfunction "TMS_0_M7") (pintype "input"))
    )
    (net (code "62") (name "/FPGA_PROGRA_B") (class "Default")
      (node (ref "R9") (pin "1") (pinfunction "1_1") (pintype "passive"))
      (node (ref "S1") (pin "1") (pinfunction "1_1") (pintype "passive"))
      (node (ref "S1") (pin "2") (pinfunction "2_2") (pintype "passive"))
      (node (ref "U2") (pin "L9") (pinfunction "PROGRAM_B_0_L9") (pintype "input"))
    )
    (net (code "63") (name "/FPGA_PUDC_B") (class "Default")
      (node (ref "R10") (pin "1") (pinfunction "1_1") (pintype "passive"))
      (node (ref "U2") (pin "L15") (pinfunction "IO_L3P_T0_DQS_PUDC_B_14_L15") (pintype "bidirectional"))
    )
    (net (code "64") (name "/FPGA_SPI_MISO") (class "Default")
      (node (ref "U2") (pin "J14") (pinfunction "IO_L1N_T0_D01_DIN_14_J14") (pintype "bidirectional"))
    )
    (net (code "65") (name "/FPGA_SPI_MOSI") (class "Default")
      (node (ref "U2") (pin "J13") (pinfunction "IO_L1P_T0_D00_MOSI_14_J13") (pintype "bidirectional"))
    )
    (net (code "66") (name "/F_CTL0") (class "Default")
      (node (ref "U2") (pin "P4") (pinfunction "IO_L5P_T0_34_P4") (pintype "bidirectional"))
    )
    (net (code "67") (name "/F_CTL1") (class "Default")
      (node (ref "U2") (pin "T5") (pinfunction "IO_L23N_T3_A02_D18_14_T5") (pintype "bidirectional"))
    )
    (net (code "68") (name "/F_CTL2") (class "Default")
      (node (ref "U2") (pin "T4") (pinfunction "IO_L9P_T1_DQS_34_T4") (pintype "bidirectional"))
    )
    (net (code "69") (name "/F_CTL3") (class "Default")
      (node (ref "U2") (pin "R5") (pinfunction "IO_L23P_T3_A03_D19_14_R5") (pintype "bidirectional"))
    )
    (net (code "70") (name "/F_CTL4") (class "Default")
      (node (ref "U2") (pin "T7") (pinfunction "IO_L21P_T3_DQS_14_T7") (pintype "bidirectional"))
    )
    (net (code "71") (name "/F_CTL5") (class "Default")
      (node (ref "U2") (pin "R7") (pinfunction "IO_L24N_T3_A00_D16_14_R7") (pintype "bidirectional"))
    )
    (net (code "72") (name "/F_CTL6") (class "Default")
      (node (ref "U2") (pin "T9") (pinfunction "IO_L22P_T3_A05_D21_14_T9") (pintype "bidirectional"))
    )
    (net (code "73") (name "/F_CTL7") (class "Default")
      (node (ref "U2") (pin "R3") (pinfunction "IO_L8P_T1_34_R3") (pintype "bidirectional"))
    )
    (net (code "74") (name "/F_CTL8") (class "Default")
      (node (ref "U2") (pin "R8") (pinfunction "IO_L20N_T3_A07_D23_14_R8") (pintype "bidirectional"))
    )
    (net (code "75") (name "/F_CTL9") (class "Default")
      (node (ref "U2") (pin "P5") (pinfunction "IO_L10P_T1_34_P5") (pintype "bidirectional"))
    )
    (net (code "76") (name "/F_CTL10") (class "Default")
      (node (ref "U2") (pin "N6") (pinfunction "IO_L19N_T3_A09_D25_VREF_14_N6") (pintype "bidirectional"))
    )
    (net (code "77") (name "/F_CTL11") (class "Default")
      (node (ref "U2") (pin "T10") (pinfunction "IO_L22N_T3_A04_D20_14_T10") (pintype "bidirectional"))
    )
    (net (code "78") (name "/F_CTL12") (class "Default")
      (node (ref "U2") (pin "R11") (pinfunction "IO_L17N_T2_A13_D29_14_R11") (pintype "bidirectional"))
    )
    (net (code "80") (name "/F_CTRL_IN0") (class "Default")
      (node (ref "U2") (pin "J5") (pinfunction "IO_L19P_T3_35_J5") (pintype "bidirectional"))
    )
    (net (code "81") (name "/F_CTRL_IN1") (class "Default")
      (node (ref "U2") (pin "E3") (pinfunction "IO_L11P_T1_SRCC_35_E3") (pintype "bidirectional"))
    )
    (net (code "82") (name "/F_CTRL_IN2") (class "Default")
      (node (ref "U2") (pin "B2") (pinfunction "IO_L8P_T1_AD14P_35_B2") (pintype "bidirectional"))
    )
    (net (code "83") (name "/F_CTRL_IN3") (class "Default")
      (node (ref "U2") (pin "B5") (pinfunction "IO_L2N_T0_AD12N_35_B5") (pintype "bidirectional"))
    )
    (net (code "85") (name "/F_CTRL_OUT0") (class "Default")
      (node (ref "U2") (pin "A5") (pinfunction "IO_L3P_T0_DQS_AD5P_35_A5") (pintype "bidirectional"))
    )
    (net (code "86") (name "/F_CTRL_OUT1") (class "Default")
      (node (ref "U2") (pin "B6") (pinfunction "IO_L2P_T0_AD12P_35_B6") (pintype "bidirectional"))
    )
    (net (code "87") (name "/F_CTRL_OUT2") (class "Default")
      (node (ref "U2") (pin "D4") (pinfunction "IO_L12P_T1_MRCC_35_D4") (pintype "bidirectional"))
    )
    (net (code "88") (name "/F_CTRL_OUT3") (class "Default")
      (node (ref "U2") (pin "C1") (pinfunction "IO_L9P_T1_DQS_AD7P_35_C1") (pintype "bidirectional"))
    )
    (net (code "89") (name "/F_CTRL_OUT4") (class "Default")
      (node (ref "U2") (pin "A4") (pinfunction "IO_L3N_T0_DQS_AD5N_35_A4") (pintype "bidirectional"))
    )
    (net (code "90") (name "/F_CTRL_OUT5") (class "Default")
      (node (ref "U2") (pin "C6") (pinfunction "IO_L5N_T0_AD13N_35_C6") (pintype "bidirectional"))
    )
    (net (code "91") (name "/F_CTRL_OUT6") (class "Default")
      (node (ref "U2") (pin "F5") (pinfunction "IO_L13P_T2_MRCC_35_F5") (pintype "bidirectional"))
    )
    (net (code "92") (name "/F_CTRL_OUT7") (class "Default")
      (node (ref "U2") (pin "B7") (pinfunction "IO_L1P_T0_AD4P_35_B7") (pintype "bidirectional"))
    )
    (net (code "94") (name "/F_DATA_CLK") (class "Default")
      (node (ref "U2") (pin "E5") (pinfunction "IO_L13N_T2_MRCC_35_E5") (pintype "bidirectional"))
    )
    (net (code "95") (name "/F_DQ0") (class "Default")
      (node (ref "U2") (pin "N1") (pinfunction "IO_L4P_T0_34_N1") (pintype "bidirectional"))
    )
    (net (code "96") (name "/F_DQ1") (class "Default")
      (node (ref "U2") (pin "R1") (pinfunction "IO_L7N_T1_34_R1") (pintype "bidirectional"))
    )
    (net (code "97") (name "/F_DQ2") (class "Default")
      (node (ref "U2") (pin "T8") (pinfunction "IO_L21N_T3_DQS_A06_D22_14_T8") (pintype "bidirectional"))
    )
    (net (code "98") (name "/F_DQ3") (class "Default")
      (node (ref "U2") (pin "M1") (pinfunction "IO_L2N_T0_34_M1") (pintype "bidirectional"))
    )
    (net (code "99") (name "/F_DQ4") (class "Default")
      (node (ref "U2") (pin "R2") (pinfunction "IO_L7P_T1_34_R2") (pintype "bidirectional"))
    )
    (net (code "100") (name "/F_DQ5") (class "Default")
      (node (ref "U2") (pin "T2") (pinfunction "IO_L8N_T1_34_T2") (pintype "bidirectional"))
    )
    (net (code "101") (name "/F_DQ6") (class "Default")
      (node (ref "U2") (pin "P1") (pinfunction "IO_L4N_T0_34_P1") (pintype "bidirectional"))
    )
    (net (code "102") (name "/F_DQ7") (class "Default")
      (node (ref "U2") (pin "T3") (pinfunction "IO_L9N_T1_DQS_34_T3") (pintype "bidirectional"))
    )
    (net (code "103") (name "/F_DQ8") (class "Default")
      (node (ref "U2") (pin "M2") (pinfunction "IO_L2P_T0_34_M2") (pintype "bidirectional"))
    )
    (net (code "104") (name "/F_DQ9") (class "Default")
      (node (ref "U2") (pin "M4") (pinfunction "IO_L1N_T0_34_M4") (pintype "bidirectional"))
    )
    (net (code "105") (name "/F_DQ10") (class "Default")
      (node (ref "U2") (pin "N4") (pinfunction "IO_L6N_T0_VREF_34_N4") (pintype "bidirectional"))
    )
    (net (code "106") (name "/F_DQ11") (class "Default")
      (node (ref "U2") (pin "L5") (pinfunction "IO_0_34_L5") (pintype "bidirectional"))
    )
    (net (code "107") (name "/F_DQ12") (class "Default")
      (node (ref "U2") (pin "N2") (pinfunction "IO_L3N_T0_DQS_34_N2") (pintype "bidirectional"))
    )
    (net (code "108") (name "/F_DQ13") (class "Default")
      (node (ref "U2") (pin "M5") (pinfunction "IO_L6P_T0_34_M5") (pintype "bidirectional"))
    )
    (net (code "109") (name "/F_DQ14") (class "Default")
      (node (ref "U2") (pin "P6") (pinfunction "IO_25_14_P6") (pintype "bidirectional"))
    )
    (net (code "110") (name "/F_DQ15") (class "Default")
      (node (ref "U2") (pin "R6") (pinfunction "IO_L24P_T3_A01_D17_14_R6") (pintype "bidirectional"))
    )
    (net (code "111") (name "/F_DQ16") (class "Default")
      (node (ref "U2") (pin "N9") (pinfunction "IO_L18P_T2_A12_D28_14_N9") (pintype "bidirectional"))
    )
    (net (code "112") (name "/F_DQ17") (class "Default")
      (node (ref "U2") (pin "P8") (pinfunction "IO_L20P_T3_A08_D24_14_P8") (pintype "bidirectional"))
    )
    (net (code "113") (name "/F_DQ18") (class "Default")
      (node (ref "U2") (pin "P9") (pinfunction "IO_L18N_T2_A11_D27_14_P9") (pintype "bidirectional"))
    )
    (net (code "114") (name "/F_DQ19") (class "Default")
      (node (ref "U2") (pin "M6") (pinfunction "IO_L19P_T3_A10_D26_14_M6") (pintype "bidirectional"))
    )
    (net (code "115") (name "/F_DQ20") (class "Default")
      (node (ref "U2") (pin "T13") (pinfunction "IO_L16N_T2_A15_D31_14_T13") (pintype "bidirectional"))
    )
    (net (code "116") (name "/F_DQ21") (class "Default")
      (node (ref "U2") (pin "P10") (pinfunction "IO_L14P_T2_SRCC_14_P10") (pintype "bidirectional"))
    )
    (net (code "117") (name "/F_DQ22") (class "Default")
      (node (ref "U2") (pin "T12") (pinfunction "IO_L15N_T2_DQS_DOUT_CSO_B_14_T12") (pintype "bidirectional"))
    )
    (net (code "118") (name "/F_DQ23") (class "Default")
      (node (ref "U2") (pin "N13") (pinfunction "IO_L11P_T1_SRCC_14_N13") (pintype "bidirectional"))
    )
    (net (code "119") (name "/F_DQ24") (class "Default")
      (node (ref "U2") (pin "P13") (pinfunction "IO_L11N_T1_SRCC_14_P13") (pintype "bidirectional"))
    )
    (net (code "120") (name "/F_DQ25") (class "Default")
      (node (ref "U2") (pin "P16") (pinfunction "IO_L8N_T1_D12_14_P16") (pintype "bidirectional"))
    )
    (net (code "121") (name "/F_DQ26") (class "Default")
      (node (ref "U2") (pin "P15") (pinfunction "IO_L8P_T1_D11_14_P15") (pintype "bidirectional"))
    )
    (net (code "122") (name "/F_DQ27") (class "Default")
      (node (ref "U2") (pin "T14") (pinfunction "IO_L10P_T1_D14_14_T14") (pintype "bidirectional"))
    )
    (net (code "123") (name "/F_DQ28") (class "Default")
      (node (ref "U2") (pin "R13") (pinfunction "IO_L16P_T2_CSI_B_14_R13") (pintype "bidirectional"))
    )
    (net (code "124") (name "/F_DQ29") (class "Default")
      (node (ref "U2") (pin "R16") (pinfunction "IO_L9N_T1_DQS_D13_14_R16") (pintype "bidirectional"))
    )
    (net (code "125") (name "/F_DQ30") (class "Default")
      (node (ref "U2") (pin "T15") (pinfunction "IO_L10N_T1_D15_14_T15") (pintype "bidirectional"))
    )
    (net (code "126") (name "/F_DQ31") (class "Default")
      (node (ref "U2") (pin "R15") (pinfunction "IO_L9P_T1_DQS_14_R15") (pintype "bidirectional"))
    )
    (net (code "128") (name "/F_ENABLE_AD9364") (class "Default")
      (node (ref "U2") (pin "D5") (pinfunction "IO_L6N_T0_VREF_35_D5") (pintype "bidirectional"))
    )
    (net (code "129") (name "/F_FB_CLK") (class "Default")
      (node (ref "U2") (pin "D1") (pinfunction "IO_L10N_T1_AD15N_35_D1") (pintype "bidirectional"))
    )
    (net (code "130") (name "/F_INT_CTL") (class "Default")
      (node (ref "U2") (pin "L4") (pinfunction "IO_L1P_T0_34_L4") (pintype "bidirectional"))
    )
    (net (code "131") (name "/F_P0_D0") (class "Default")
      (node (ref "U2") (pin "H2") (pinfunction "IO_L20P_T3_35_H2") (pintype "bidirectional"))
    )
    (net (code "132") (name "/F_P0_D1") (class "Default")
      (node (ref "U2") (pin "G1") (pinfunction "IO_L17N_T2_35_G1") (pintype "bidirectional"))
    )
    (net (code "133") (name "/F_P0_D2") (class "Default")
      (node (ref "U2") (pin "H1") (pinfunction "IO_L20N_T3_35_H1") (pintype "bidirectional"))
    )
    (net (code "134") (name "/F_P0_D3") (class "Default")
      (node (ref "U2") (pin "B1") (pinfunction "IO_L9N_T1_DQS_AD7N_35_B1") (pintype "bidirectional"))
    )
    (net (code "135") (name "/F_P0_D4") (class "Default")
      (node (ref "U2") (pin "C3") (pinfunction "IO_L7P_T1_AD6P_35_C3") (pintype "bidirectional"))
    )
    (net (code "136") (name "/F_P0_D5") (class "Default")
      (node (ref "U2") (pin "G2") (pinfunction "IO_L17P_T2_35_G2") (pintype "bidirectional"))
    )
    (net (code "137") (name "/F_P0_D6") (class "Default")
      (node (ref "U2") (pin "A2") (pinfunction "IO_L8N_T1_AD14N_35_A2") (pintype "bidirectional"))
    )
    (net (code "138") (name "/F_P0_D7") (class "Default")
      (node (ref "U2") (pin "F2") (pinfunction "IO_L15P_T2_DQS_35_F2") (pintype "bidirectional"))
    )
    (net (code "139") (name "/F_P0_D8") (class "Default")
      (node (ref "U2") (pin "E1") (pinfunction "IO_L15N_T2_DQS_35_E1") (pintype "bidirectional"))
    )
    (net (code "140") (name "/F_P0_D9") (class "Default")
      (node (ref "U2") (pin "E2") (pinfunction "IO_L10P_T1_AD15P_35_E2") (pintype "bidirectional"))
    )
    (net (code "141") (name "/F_P0_D10") (class "Default")
      (node (ref "U2") (pin "C2") (pinfunction "IO_L7N_T1_AD6N_35_C2") (pintype "bidirectional"))
    )
    (net (code "142") (name "/F_P0_D11") (class "Default")
      (node (ref "U2") (pin "A3") (pinfunction "IO_L4N_T0_35_A3") (pintype "bidirectional"))
    )
    (net (code "144") (name "/F_P1_D0") (class "Default")
      (node (ref "U2") (pin "K3") (pinfunction "IO_L24P_T3_35_K3") (pintype "bidirectional"))
    )
    (net (code "145") (name "/F_P1_D1") (class "Default")
      (node (ref "U2") (pin "K2") (pinfunction "IO_L24N_T3_35_K2") (pintype "bidirectional"))
    )
    (net (code "146") (name "/F_P1_D2") (class "Default")
      (node (ref "U2") (pin "H4") (pinfunction "IO_L18N_T2_35_H4") (pintype "bidirectional"))
    )
    (net (code "147") (name "/F_P1_D3") (class "Default")
      (node (ref "U2") (pin "J1") (pinfunction "IO_L22N_T3_35_J1") (pintype "bidirectional"))
    )
    (net (code "148") (name "/F_P1_D4") (class "Default")
      (node (ref "U2") (pin "L2") (pinfunction "IO_L23N_T3_35_L2") (pintype "bidirectional"))
    )
    (net (code "149") (name "/F_P1_D5") (class "Default")
      (node (ref "U2") (pin "K1") (pinfunction "IO_L22P_T3_35_K1") (pintype "bidirectional"))
    )
    (net (code "150") (name "/F_P1_D6") (class "Default")
      (node (ref "U2") (pin "L3") (pinfunction "IO_L23P_T3_35_L3") (pintype "bidirectional"))
    )
    (net (code "151") (name "/F_P1_D7") (class "Default")
      (node (ref "U2") (pin "G4") (pinfunction "IO_L16N_T2_35_G4") (pintype "bidirectional"))
    )
    (net (code "152") (name "/F_P1_D8") (class "Default")
      (node (ref "U2") (pin "H3") (pinfunction "IO_L21N_T3_DQS_35_H3") (pintype "bidirectional"))
    )
    (net (code "153") (name "/F_P1_D9") (class "Default")
      (node (ref "U2") (pin "F3") (pinfunction "IO_L14N_T2_SRCC_35_F3") (pintype "bidirectional"))
    )
    (net (code "154") (name "/F_P1_D10") (class "Default")
      (node (ref "U2") (pin "J3") (pinfunction "IO_L21P_T3_DQS_35_J3") (pintype "bidirectional"))
    )
    (net (code "155") (name "/F_P1_D11") (class "Default")
      (node (ref "U2") (pin "B4") (pinfunction "IO_L4P_T0_35_B4") (pintype "bidirectional"))
    )
    (net (code "157") (name "/F_PCLK") (class "Default")
      (node (ref "U2") (pin "N11") (pinfunction "IO_L13P_T2_MRCC_14_N11") (pintype "bidirectional"))
    )
    (net (code "158") (name "/F_RX_FRAME") (class "Default")
      (node (ref "U2") (pin "D3") (pinfunction "IO_L11N_T1_SRCC_35_D3") (pintype "bidirectional"))
    )
    (net (code "159") (name "/F_TX_FRAME") (class "Default")
      (node (ref "U2") (pin "J4") (pinfunction "IO_L19N_T3_VREF_35_J4") (pintype "bidirectional"))
    )
    (net (code "160") (name "/GPIO0") (class "Default")
      (node (ref "U2") (pin "K15") (pinfunction "IO_L2P_T0_D02_14_K15") (pintype "bidirectional"))
    )
    (net (code "161") (name "/GPIO1") (class "Default")
      (node (ref "U2") (pin "M16") (pinfunction "IO_L7P_T1_D09_14_M16") (pintype "bidirectional"))
    )
    (net (code "162") (name "/GPIO2") (class "Default")
      (node (ref "U2") (pin "K13") (pinfunction "IO_L5P_T0_D06_14_K13") (pintype "bidirectional"))
    )
    (net (code "163") (name "/GPIO3") (class "Default")
      (node (ref "U2") (pin "K12") (pinfunction "IO_0_14_K12") (pintype "bidirectional"))
    )
    (net (code "164") (name "/GPIO4") (class "Default")
      (node (ref "U2") (pin "N14") (pinfunction "IO_L12P_T1_MRCC_14_N14") (pintype "bidirectional"))
    )
    (net (code "165") (name "/GPIO5") (class "Default")
      (node (ref "U2") (pin "R12") (pinfunction "IO_L15P_T2_DQS_RDWR_B_14_R12") (pintype "bidirectional"))
    )
    (net (code "167") (name "/INIT_B") (class "Default")
      (node (ref "R11") (pin "1") (pinfunction "1_1") (pintype "passive"))
      (node (ref "U2") (pin "K10") (pinfunction "INIT_B_0_K10") (pintype "bidirectional"))
    )
    (net (code "168") (name "/LEDS0") (class "Default")
      (node (ref "U2") (pin "K16") (pinfunction "IO_L2N_T0_D03_14_K16") (pintype "bidirectional"))
    )
    (net (code "169") (name "/LEDS1") (class "Default")
      (node (ref "U2") (pin "M14") (pinfunction "IO_L4N_T0_D05_14_M14") (pintype "bidirectional"))
    )
    (net (code "170") (name "/LEDS2") (class "Default")
      (node (ref "U2") (pin "L14") (pinfunction "IO_L4P_T0_D04_14_L14") (pintype "bidirectional"))
    )
    (net (code "171") (name "/LEDS3") (class "Default")
      (node (ref "U2") (pin "N16") (pinfunction "IO_L7N_T1_D10_14_N16") (pintype "bidirectional"))
    )
    (net (code "172") (name "/LEDS4") (class "Default")
      (node (ref "U2") (pin "L13") (pinfunction "IO_L5N_T0_D07_14_L13") (pintype "bidirectional"))
    )
    (net (code "173") (name "/LEDS5") (class "Default")
      (node (ref "U2") (pin "K5") (pinfunction "IO_25_35_K5") (pintype "bidirectional"))
    )
    (net (code "174") (name "/LEDS6") (class "Default")
      (node (ref "U2") (pin "N3") (pinfunction "IO_L3P_T0_DQS_34_N3") (pintype "bidirectional"))
    )
    (net (code "175") (name "/LEDS7") (class "Default")
      (node (ref "U2") (pin "P3") (pinfunction "IO_L5N_T0_34_P3") (pintype "bidirectional"))
    )
    (net (code "177") (name "/M0") (class "Default")
      (node (ref "R14") (pin "1") (pinfunction "1_1") (pintype "passive"))
      (node (ref "U2") (pin "M9") (pinfunction "M0_0_M9") (pintype "input"))
    )
    (net (code "178") (name "/M1") (class "Default")
      (node (ref "R15") (pin "1") (pinfunction "1_1") (pintype "passive"))
      (node (ref "U2") (pin "M10") (pinfunction "M1_0_M10") (pintype "input"))
    )
    (net (code "179") (name "/M2") (class "Default")
      (node (ref "R16") (pin "1") (pinfunction "1_1") (pintype "passive"))
      (node (ref "U2") (pin "M11") (pinfunction "M2_0_M11") (pintype "input"))
    )
    (net (code "180") (name "/SPI_CLK_F") (class "Default")
      (node (ref "U2") (pin "A7") (pinfunction "IO_L1N_T0_AD4N_35_A7") (pintype "bidirectional"))
    )
    (net (code "181") (name "/SPI_DI_F") (class "Default")
      (node (ref "U2") (pin "F4") (pinfunction "IO_L14P_T2_SRCC_35_F4") (pintype "bidirectional"))
    )
    (net (code "182") (name "/SPI_DO_F") (class "Default")
      (node (ref "U2") (pin "H5") (pinfunction "IO_L18P_T2_35_H5") (pintype "bidirectional"))
    )
    (net (code "183") (name "/SPI_EN_F") (class "Default")
      (node (ref "U2") (pin "G5") (pinfunction "IO_L16P_T2_35_G5") (pintype "bidirectional"))
    )
    (net (code "184") (name "/SYNC_IN_F") (class "Default")
      (node (ref "U2") (pin "D6") (pinfunction "IO_L6P_T0_35_D6") (pintype "bidirectional"))
    )
    (net (code "185") (name "/TXNRX_F") (class "Default")
      (node (ref "U2") (pin "E6") (pinfunction "IO_0_35_E6") (pintype "bidirectional"))
    )
    (net (code "186") (name "1.8V") (class "Default")
      (node (ref "P3") (pin "2") (pinfunction "2_2") (pintype "passive"))
    )
    (net (code "187") (name "1.8V_F") (class "Default")
      (node (ref "C27") (pin "1") (pinfunction "1_1") (pintype "passive"))
      (node (ref "C28") (pin "1") (pinfunction "1_1") (pintype "passive"))
      (node (ref "C29") (pin "1") (pinfunction "1_1") (pintype "passive"))
      (node (ref "C30") (pin "1") (pinfunction "1_1") (pintype "passive"))
      (node (ref "C31") (pin "1") (pinfunction "1_1") (pintype "passive"))
      (node (ref "C32") (pin "1") (pinfunction "1_1") (pintype "passive"))
      (node (ref "C33") (pin "1") (pinfunction "1_1") (pintype "passive"))
      (node (ref "C34") (pin "1") (pinfunction "1_1") (pintype "passive"))
      (node (ref "C35") (pin "1") (pinfunction "1_1") (pintype "passive"))
      (node (ref "C36") (pin "1") (pinfunction "1_1") (pintype "passive"))
      (node (ref "C37") (pin "1") (pinfunction "1_1") (pintype "passive"))
      (node (ref "C38") (pin "1") (pinfunction "1_1") (pintype "passive"))
      (node (ref "C40") (pin "1") (pinfunction "1_1") (pintype "passive"))
      (node (ref "C46") (pin "1") (pinfunction "1_1") (pintype "passive"))
      (node (ref "C47") (pin "1") (pinfunction "1_1") (pintype "passive"))
      (node (ref "C48") (pin "1") (pinfunction "1_1") (pintype "passive"))
      (node (ref "C49") (pin "1") (pinfunction "1_1") (pintype "passive"))
      (node (ref "C50") (pin "1") (pinfunction "1_1") (pintype "passive"))
      (node (ref "C51") (pin "1") (pinfunction "1_1") (pintype "passive"))
      (node (ref "C52") (pin "1") (pinfunction "1_1") (pintype "passive"))
      (node (ref "C53") (pin "1") (pinfunction "1_1") (pintype "passive"))
      (node (ref "C54") (pin "1") (pinfunction "1_1") (pintype "passive"))
      (node (ref "C55") (pin "1") (pinfunction "1_1") (pintype "passive"))
      (node (ref "C56") (pin "1") (pinfunction "1_1") (pintype "passive"))
      (node (ref "C57") (pin "1") (pinfunction "1_1") (pintype "passive"))
      (node (ref "C58") (pin "1") (pinfunction "1_1") (pintype "passive"))
      (node (ref "C59") (pin "1") (pinfunction "1_1") (pintype "passive"))
      (node (ref "C62") (pin "1") (pinfunction "1_1") (pintype "passive"))
      (node (ref "P2") (pin "2") (pinfunction "2_2") (pintype "passive"))
      (node (ref "P3") (pin "1") (pinfunction "1_1") (pintype "passive"))
      (node (ref "R11") (pin "2") (pinfunction "2_2") (pintype "passive"))
      (node (ref "R12") (pin "2") (pinfunction "2_2") (pintype "passive"))
      (node (ref "R14") (pin "2") (pinfunction "2_2") (pintype "passive"))
      (node (ref "R15") (pin "2") (pinfunction "2_2") (pintype "passive"))
      (node (ref "R16") (pin "2") (pinfunction "2_2") (pintype "passive"))
      (node (ref "R9") (pin "2") (pinfunction "2_2") (pintype "passive"))
      (node (ref "R97") (pin "1") (pinfunction "1_1") (pintype "passive"))
      (node (ref "U2") (pin "A6") (pinfunction "VCCO_35_A6") (pintype "power_in"))
      (node (ref "U2") (pin "B3") (pinfunction "VCCO_35_B3") (pintype "power_in"))
      (node (ref "U2") (pin "D7") (pinfunction "VCCO_35_D7") (pintype "power_in"))
      (node (ref "U2") (pin "E4") (pinfunction "VCCO_35_E4") (pintype "power_in"))
      (node (ref "U2") (pin "E7") (pinfunction "CFGBVS_0_E7") (pintype "input"))
      (node (ref "U2") (pin "F1") (pinfunction "VCCO_35_F1") (pintype "power_in"))
      (node (ref "U2") (pin "G10") (pinfunction "VCCAUX_G10") (pintype "power_in"))
      (node (ref "U2") (pin "G8") (pinfunction "VCCADC_0_G8") (pintype "power_in"))
      (node (ref "U2") (pin "J10") (pinfunction "VCCAUX_J10") (pintype "power_in"))
      (node (ref "U2") (pin "J2") (pinfunction "VCCO_35_J2") (pintype "power_in"))
      (node (ref "U2") (pin "K11") (pinfunction "VCCAUX_K11") (pintype "power_in"))
      (node (ref "U2") (pin "L10") (pinfunction "VCCAUX_L10") (pintype "power_in"))
      (node (ref "U2") (pin "L16") (pinfunction "VCCO_14_L16") (pintype "power_in"))
      (node (ref "U2") (pin "L6") (pinfunction "VCCO_0_L6") (pintype "power_in"))
      (node (ref "U2") (pin "M13") (pinfunction "VCCO_14_M13") (pintype "power_in"))
      (node (ref "U2") (pin "M3") (pinfunction "VCCO_34_M3") (pintype "power_in"))
      (node (ref "U2") (pin "N10") (pinfunction "VCCO_14_N10") (pintype "power_in"))
      (node (ref "U2") (pin "P7") (pinfunction "VCCO_14_P7") (pintype "power_in"))
      (node (ref "U2") (pin "R14") (pinfunction "VCCO_14_R14") (pintype "power_in"))
      (node (ref "U2") (pin "R4") (pinfunction "VCCO_34_R4") (pintype "power_in"))
      (node (ref "U2") (pin "T1") (pinfunction "VCCO_34_T1") (pintype "power_in"))
      (node (ref "U2") (pin "T11") (pinfunction "VCCO_14_T11") (pintype "power_in"))
      (node (ref "Y2") (pin "4") (pinfunction "VDD_4") (pintype "passive"))
    )
    (net (code "188") (name "1V") (class "Default")
      (node (ref "P1") (pin "2") (pinfunction "2_2") (pintype "passive"))
    )
    (net (code "189") (name "1V_F") (class "Default")
      (node (ref "C13") (pin "1") (pinfunction "1_1") (pintype "passive"))
      (node (ref "C14") (pin "1") (pinfunction "1_1") (pintype "passive"))
      (node (ref "C15") (pin "1") (pinfunction "1_1") (pintype "passive"))
      (node (ref "C16") (pin "1") (pinfunction "1_1") (pintype "passive"))
      (node (ref "C17") (pin "1") (pinfunction "1_1") (pintype "passive"))
      (node (ref "C18") (pin "1") (pinfunction "1_1") (pintype "passive"))
      (node (ref "C19") (pin "1") (pinfunction "1_1") (pintype "passive"))
      (node (ref "C20") (pin "1") (pinfunction "1_1") (pintype "passive"))
      (node (ref "C21") (pin "1") (pinfunction "1_1") (pintype "passive"))
      (node (ref "C22") (pin "1") (pinfunction "1_1") (pintype "passive"))
      (node (ref "C23") (pin "1") (pinfunction "1_1") (pintype "passive"))
      (node (ref "C24") (pin "1") (pinfunction "1_1") (pintype "passive"))
      (node (ref "C25") (pin "1") (pinfunction "1_1") (pintype "passive"))
      (node (ref "C26") (pin "1") (pinfunction "1_1") (pintype "passive"))
      (node (ref "P1") (pin "1") (pinfunction "1_1") (pintype "passive"))
      (node (ref "U2") (pin "E10") (pinfunction "VCCBRAM_E10") (pintype "power_in"))
      (node (ref "U2") (pin "F11") (pinfunction "VCCBRAM_F11") (pintype "power_in"))
      (node (ref "U2") (pin "F7") (pinfunction "VCCINT_F7") (pintype "power_in"))
      (node (ref "U2") (pin "F9") (pinfunction "VCCINT_F9") (pintype "power_in"))
      (node (ref "U2") (pin "G6") (pinfunction "VCCINT_G6") (pintype "power_in"))
      (node (ref "U2") (pin "H9") (pinfunction "VCCINT_H9") (pintype "power_in"))
      (node (ref "U2") (pin "J6") (pinfunction "VCCINT_J6") (pintype "power_in"))
      (node (ref "U2") (pin "K9") (pinfunction "VCCINT_K9") (pintype "power_in"))
      (node (ref "U2") (pin "L8") (pinfunction "VCCINT_L8") (pintype "power_in"))
    )
    (net (code "190") (name "3.3V") (class "Default")
      (node (ref "R13") (pin "2") (pinfunction "2_2") (pintype "passive"))
    )
    (net (code "191") (name "GND") (class "Default")
      (node (ref "C13") (pin "2") (pinfunction "2_2") (pintype "passive"))
      (node (ref "C14") (pin "2") (pinfunction "2_2") (pintype "passive"))
      (node (ref "C15") (pin "2") (pinfunction "2_2") (pintype "passive"))
      (node (ref "C16") (pin "2") (pinfunction "2_2") (pintype "passive"))
      (node (ref "C17") (pin "2") (pinfunction "2_2") (pintype "passive"))
      (node (ref "C18") (pin "2") (pinfunction "2_2") (pintype "passive"))
      (node (ref "C19") (pin "2") (pinfunction "2_2") (pintype "passive"))
      (node (ref "C20") (pin "2") (pinfunction "2_2") (pintype "passive"))
      (node (ref "C21") (pin "2") (pinfunction "2_2") (pintype "passive"))
      (node (ref "C22") (pin "2") (pinfunction "2_2") (pintype "passive"))
      (node (ref "C23") (pin "2") (pinfunction "2_2") (pintype "passive"))
      (node (ref "C24") (pin "2") (pinfunction "2_2") (pintype "passive"))
      (node (ref "C25") (pin "2") (pinfunction "2_2") (pintype "passive"))
      (node (ref "C26") (pin "2") (pinfunction "2_2") (pintype "passive"))
      (node (ref "C27") (pin "2") (pinfunction "2_2") (pintype "passive"))
      (node (ref "C28") (pin "2") (pinfunction "2_2") (pintype "passive"))
      (node (ref "C29") (pin "2") (pinfunction "2_2") (pintype "passive"))
      (node (ref "C30") (pin "2") (pinfunction "2_2") (pintype "passive"))
      (node (ref "C31") (pin "2") (pinfunction "2_2") (pintype "passive"))
      (node (ref "C32") (pin "2") (pinfunction "2_2") (pintype "passive"))
      (node (ref "C33") (pin "2") (pinfunction "2_2") (pintype "passive"))
      (node (ref "C34") (pin "2") (pinfunction "2_2") (pintype "passive"))
      (node (ref "C35") (pin "2") (pinfunction "2_2") (pintype "passive"))
      (node (ref "C36") (pin "2") (pinfunction "2_2") (pintype "passive"))
      (node (ref "C37") (pin "2") (pinfunction "2_2") (pintype "passive"))
      (node (ref "C38") (pin "2") (pinfunction "2_2") (pintype "passive"))
      (node (ref "C39") (pin "2") (pinfunction "2_2") (pintype "passive"))
      (node (ref "C40") (pin "2") (pinfunction "2_2") (pintype "passive"))
      (node (ref "C41") (pin "2") (pinfunction "2_2") (pintype "passive"))
      (node (ref "C42") (pin "2") (pinfunction "2_2") (pintype "passive"))
      (node (ref "C43") (pin "2") (pinfunction "2_2") (pintype "passive"))
      (node (ref "C44") (pin "2") (pinfunction "2_2") (pintype "passive"))
      (node (ref "C45") (pin "2") (pinfunction "2_2") (pintype "passive"))
      (node (ref "C46") (pin "2") (pinfunction "2_2") (pintype "passive"))
      (node (ref "C47") (pin "2") (pinfunction "2_2") (pintype "passive"))
      (node (ref "C48") (pin "2") (pinfunction "2_2") (pintype "passive"))
      (node (ref "C49") (pin "2") (pinfunction "2_2") (pintype "passive"))
      (node (ref "C50") (pin "2") (pinfunction "2_2") (pintype "passive"))
      (node (ref "C51") (pin "2") (pinfunction "2_2") (pintype "passive"))
      (node (ref "C52") (pin "2") (pinfunction "2_2") (pintype "passive"))
      (node (ref "C53") (pin "2") (pinfunction "2_2") (pintype "passive"))
      (node (ref "C54") (pin "2") (pinfunction "2_2") (pintype "passive"))
      (node (ref "C55") (pin "2") (pinfunction "2_2") (pintype "passive"))
      (node (ref "C56") (pin "2") (pinfunction "2_2") (pintype "passive"))
      (node (ref "C57") (pin "2") (pinfunction "2_2") (pintype "passive"))
      (node (ref "C58") (pin "2") (pinfunction "2_2") (pintype "passive"))
      (node (ref "C59") (pin "2") (pinfunction "2_2") (pintype "passive"))
      (node (ref "C62") (pin "2") (pinfunction "2_2") (pintype "passive"))
      (node (ref "P2") (pin "1") (pinfunction "1_1") (pintype "passive"))
      (node (ref "P2") (pin "11") (pinfunction "11_11") (pintype "passive"))
      (node (ref "P2") (pin "13") (pinfunction "13_13") (pintype "passive"))
      (node (ref "P2") (pin "3") (pinfunction "3_3") (pintype "passive"))
      (node (ref "P2") (pin "5") (pinfunction "5_5") (pintype "passive"))
      (node (ref "P2") (pin "7") (pinfunction "7_7") (pintype "passive"))
      (node (ref "P2") (pin "9") (pinfunction "9_9") (pintype "passive"))
      (node (ref "Q4") (pin "3") (pinfunction "S_3") (pintype "passive"))
      (node (ref "R10") (pin "2") (pinfunction "2_2") (pintype "passive"))
      (node (ref "S1") (pin "3") (pinfunction "3_3") (pintype "passive"))
      (node (ref "S1") (pin "4") (pinfunction "4_4") (pintype "passive"))
      (node (ref "U2") (pin "A1") (pinfunction "GND_A1") (pintype "power_in"))
      (node (ref "U2") (pin "A11") (pinfunction "GND_A11") (pintype "power_in"))
      (node (ref "U2") (pin "B8") (pinfunction "GND_B8") (pintype "power_in"))
      (node (ref "U2") (pin "C15") (pinfunction "GND_C15") (pintype "power_in"))
      (node (ref "U2") (pin "C5") (pinfunction "GND_C5") (pintype "power_in"))
      (node (ref "U2") (pin "D12") (pinfunction "GND_D12") (pintype "power_in"))
      (node (ref "U2") (pin "D2") (pinfunction "GND_D2") (pintype "power_in"))
      (node (ref "U2") (pin "E9") (pinfunction "GND_E9") (pintype "power_in"))
      (node (ref "U2") (pin "F10") (pinfunction "GND_F10") (pintype "power_in"))
      (node (ref "U2") (pin "F16") (pinfunction "GND_F16") (pintype "power_in"))
      (node (ref "U2") (pin "F6") (pinfunction "GND_F6") (pintype "power_in"))
      (node (ref "U2") (pin "F8") (pinfunction "VCCBATT_0_F8") (pintype "power_in"))
      (node (ref "U2") (pin "G13") (pinfunction "GND_G13") (pintype "power_in"))
      (node (ref "U2") (pin "G3") (pinfunction "GND_G3") (pintype "power_in"))
      (node (ref "U2") (pin "G9") (pinfunction "GND_G9") (pintype "power_in"))
      (node (ref "U2") (pin "H6") (pinfunction "GND_H6") (pintype "power_in"))
      (node (ref "U2") (pin "H7") (pinfunction "VREFN_0_H7") (pintype "input"))
      (node (ref "U2") (pin "J11") (pinfunction "GND_J11") (pintype "power_in"))
      (node (ref "U2") (pin "J8") (pinfunction "VREFP_0_J8") (pintype "input"))
      (node (ref "U2") (pin "J9") (pinfunction "GND_J9") (pintype "power_in"))
      (node (ref "U2") (pin "K14") (pinfunction "GND_K14") (pintype "power_in"))
      (node (ref "U2") (pin "K4") (pinfunction "GND_K4") (pintype "power_in"))
      (node (ref "U2") (pin "K6") (pinfunction "GND_K6") (pintype "power_in"))
      (node (ref "U2") (pin "K7") (pinfunction "DXN_0_K7") (pintype "input"))
      (node (ref "U2") (pin "K8") (pinfunction "DXP_0_K8") (pintype "input"))
      (node (ref "U2") (pin "L1") (pinfunction "GND_L1") (pintype "power_in"))
      (node (ref "U2") (pin "L11") (pinfunction "GND_L11") (pintype "power_in"))
      (node (ref "U2") (pin "M8") (pinfunction "GND_M8") (pintype "power_in"))
      (node (ref "U2") (pin "N15") (pinfunction "GND_N15") (pintype "power_in"))
      (node (ref "U2") (pin "N5") (pinfunction "GND_N5") (pintype "power_in"))
      (node (ref "U2") (pin "P12") (pinfunction "GND_P12") (pintype "power_in"))
      (node (ref "U2") (pin "P2") (pinfunction "GND_P2") (pintype "power_in"))
      (node (ref "U2") (pin "R9") (pinfunction "GND_R9") (pintype "power_in"))
      (node (ref "U2") (pin "T16") (pinfunction "GND_T16") (pintype "power_in"))
      (node (ref "U2") (pin "T6") (pinfunction "GND_T6") (pintype "power_in"))
      (node (ref "Y2") (pin "2") (pinfunction "GND_2") (pintype "passive"))
    )
    (net (code "192") (name "Net-(D1-A)") (class "Default")
      (node (ref "D1") (pin "1") (pinfunction "A_1") (pintype "passive"))
      (node (ref "R13") (pin "1") (pinfunction "1_1") (pintype "passive"))
    )
    (net (code "193") (name "Net-(D1-K)") (class "Default")
      (node (ref "D1") (pin "2") (pinfunction "K_2") (pintype "passive"))
      (node (ref "Q4") (pin "2") (pinfunction "D_2") (pintype "passive"))
    )
    (net (code "194") (name "Net-(Y2-StandBy)") (class "Default")
      (node (ref "R97") (pin "2") (pinfunction "2_2") (pintype "passive"))
      (node (ref "Y2") (pin "1") (pinfunction "StandBy_1") (pintype "passive"))
    )
    (net (code "195") (name "VDDR") (class "Default")
      (node (ref "C39") (pin "1") (pinfunction "1_1") (pintype "passive"))
      (node (ref "C41") (pin "1") (pinfunction "1_1") (pintype "passive"))
      (node (ref "C42") (pin "1") (pinfunction "1_1") (pintype "passive"))
      (node (ref "C43") (pin "1") (pinfunction "1_1") (pintype "passive"))
      (node (ref "C44") (pin "1") (pinfunction "1_1") (pintype "passive"))
      (node (ref "C45") (pin "1") (pinfunction "1_1") (pintype "passive"))
      (node (ref "U2") (pin "A16") (pinfunction "VCCO_15_A16") (pintype "power_in"))
      (node (ref "U2") (pin "B13") (pinfunction "VCCO_15_B13") (pintype "power_in"))
      (node (ref "U2") (pin "C10") (pinfunction "VCCO_15_C10") (pintype "power_in"))
      (node (ref "U2") (pin "E14") (pinfunction "VCCO_15_E14") (pintype "power_in"))
      (node (ref "U2") (pin "H15") (pinfunction "VCCO_15_H15") (pintype "power_in"))
      (node (ref "U2") (pin "J12") (pinfunction "VCCO_15_J12") (pintype "power_in"))
    )
    (net (code "196") (name "unconnected-(P2-Pad12)") (class "Default")
      (node (ref "P2") (pin "12") (pinfunction "12_12") (pintype "passive+no_connect"))
    )
    (net (code "197") (name "unconnected-(P2-Pad14)") (class "Default")
      (node (ref "P2") (pin "14") (pinfunction "14_14") (pintype "passive+no_connect"))
    )
    (net (code "198") (name "unconnected-(U2A-IO_L3N_T0_DQS_EMCCLK_14-PadM15)") (class "Default")
      (node (ref "U2") (pin "M15") (pinfunction "IO_L3N_T0_DQS_EMCCLK_14_M15") (pintype "bidirectional"))
    )
    (net (code "199") (name "unconnected-(U2A-IO_L6N_T0_D08_VREF_14-PadM12)") (class "Default")
      (node (ref "U2") (pin "M12") (pinfunction "IO_L6N_T0_D08_VREF_14_M12") (pintype "bidirectional"))
    )
    (net (code "200") (name "unconnected-(U2A-IO_L13N_T2_MRCC_14-PadN12)") (class "Default")
      (node (ref "U2") (pin "N12") (pinfunction "IO_L13N_T2_MRCC_14_N12") (pintype "bidirectional"))
    )
    (net (code "201") (name "unconnected-(U2A-IO_L14N_T2_SRCC_14-PadP11)") (class "Default")
      (node (ref "U2") (pin "P11") (pinfunction "IO_L14N_T2_SRCC_14_P11") (pintype "bidirectional"))
    )
    (net (code "202") (name "unconnected-(U2A-IO_L17P_T2_A14_D30_14-PadR10)") (class "Default")
      (node (ref "U2") (pin "R10") (pinfunction "IO_L17P_T2_A14_D30_14_R10") (pintype "bidirectional"))
    )
    (net (code "203") (name "unconnected-(U2B-IO_25_15-PadG11)") (class "Default")
      (node (ref "U2") (pin "G11") (pinfunction "IO_25_15_G11") (pintype "bidirectional"))
    )
    (net (code "204") (name "unconnected-(U2B-IO_L18P_T2_A24_15-PadF15)") (class "Default")
      (node (ref "U2") (pin "F15") (pinfunction "IO_L18P_T2_A24_15_F15") (pintype "bidirectional"))
    )
    (net (code "205") (name "unconnected-(U2B-IO_L24N_T3_RS0_15-PadG15)") (class "Default")
      (node (ref "U2") (pin "G15") (pinfunction "IO_L24N_T3_RS0_15_G15") (pintype "bidirectional"))
    )
    (net (code "206") (name "unconnected-(U2E-VN_0-PadJ7)") (class "Default")
      (node (ref "U2") (pin "J7") (pinfunction "VN_0_J7") (pintype "input+no_connect"))
    )
    (net (code "207") (name "unconnected-(U2E-VP_0-PadH8)") (class "Default")
      (node (ref "U2") (pin "H8") (pinfunction "VP_0_H8") (pintype "input+no_connect"))
    )
    (net (code "208") (name "unconnected-(U2H-GNDADC_0-PadG7)") (class "Default")
      (node (ref "U2") (pin "G7") (pinfunction "GNDADC_0_G7") (pintype "power_in"))
    )
  )
)
